# schetamic.net
KiCad netlist of a schematic drawn in EAGLE
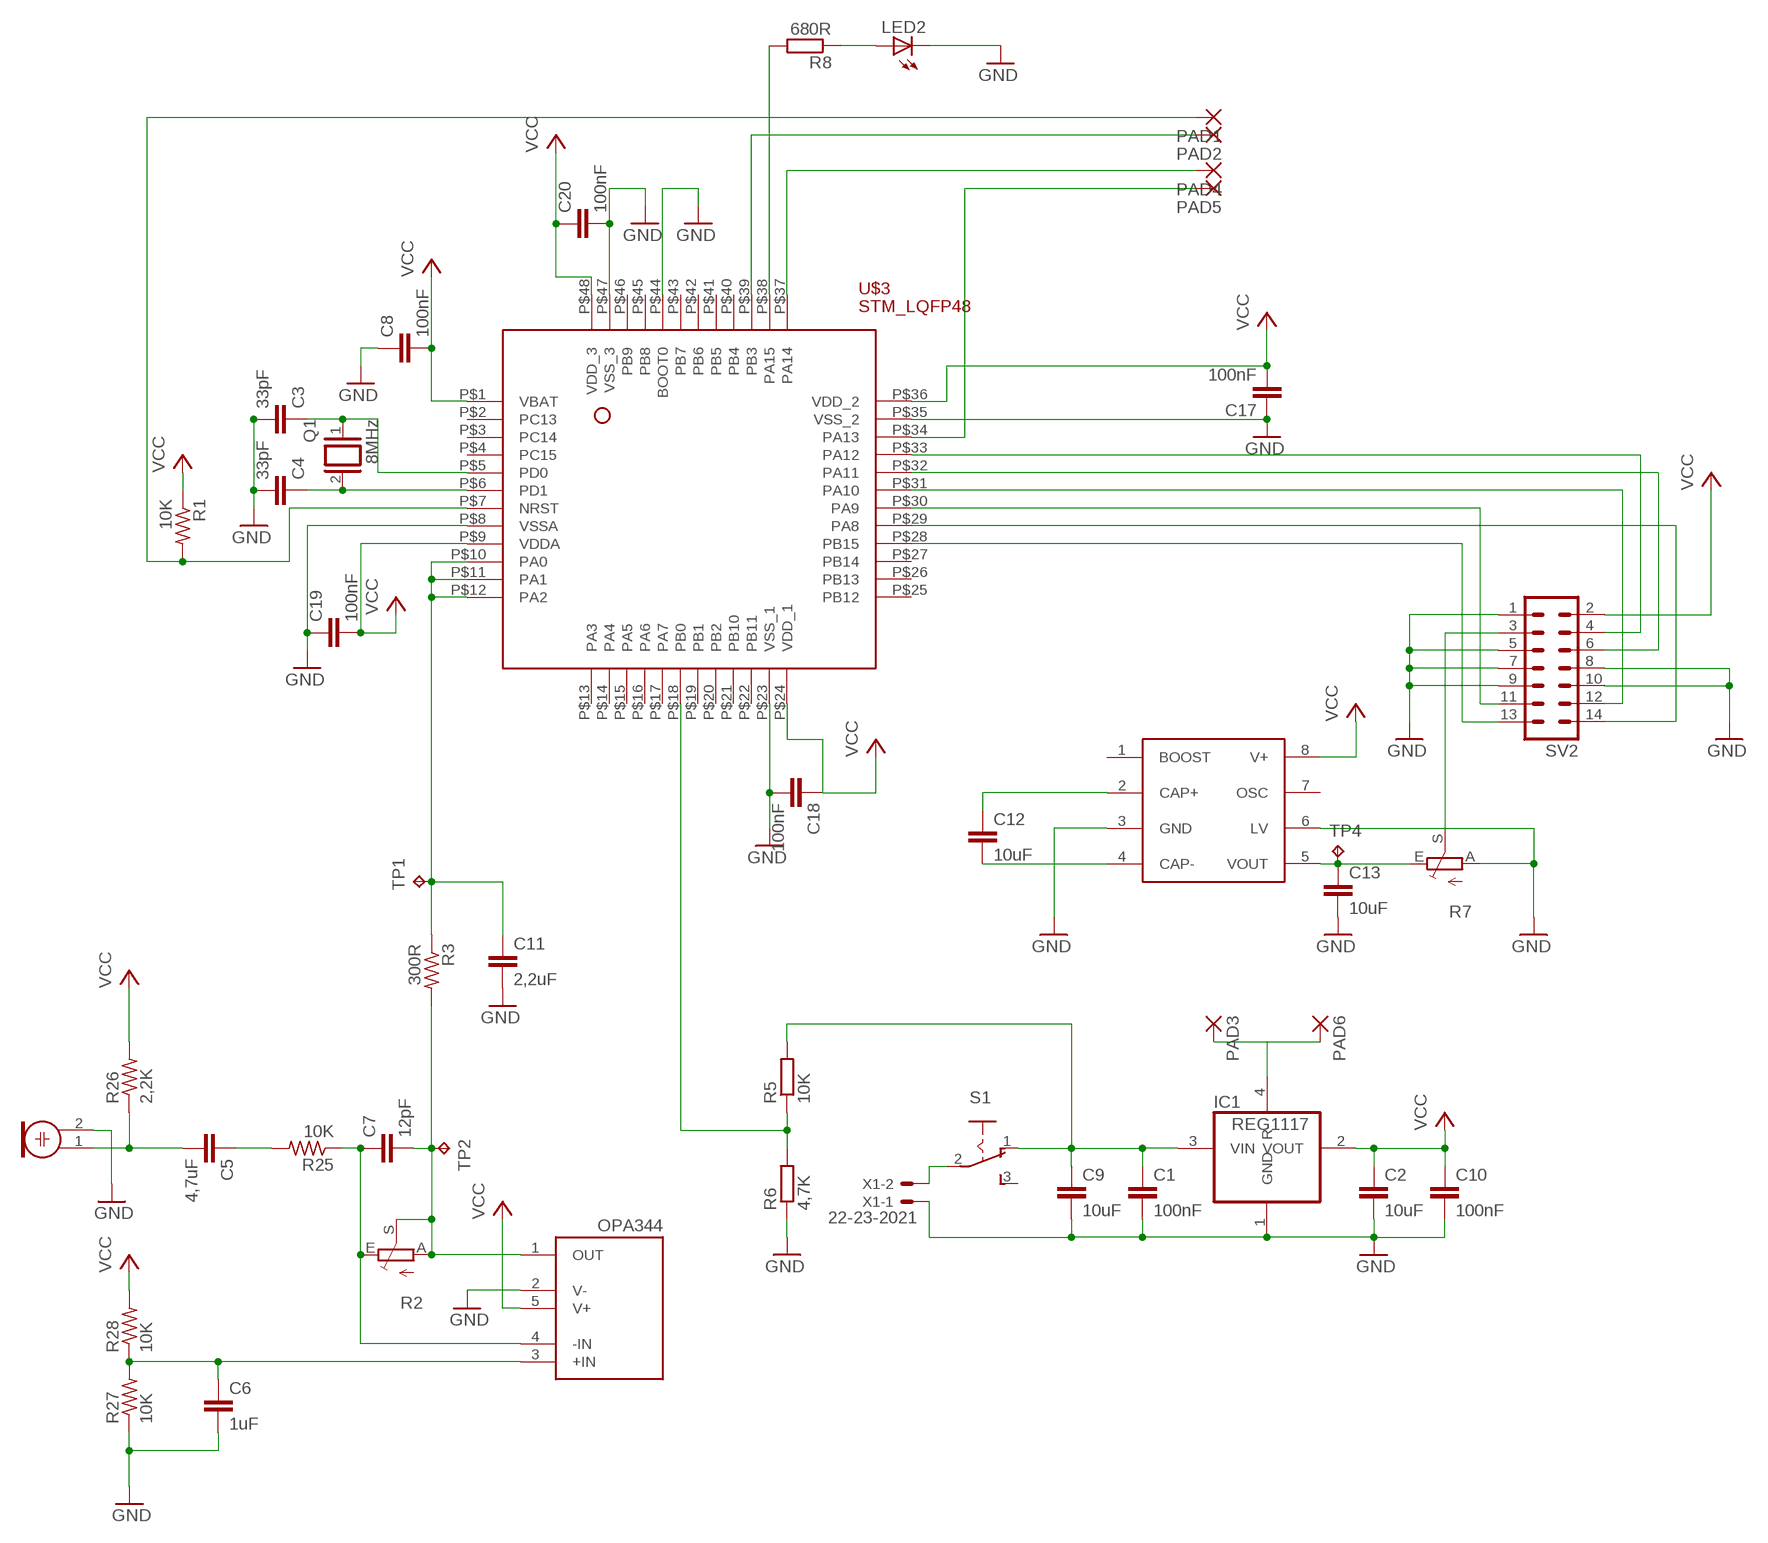
[diagram p0: schematic, sheet 1]

(export (version "E")
  (design (tool "Eeschema 10.0.6"))
  (components
    (comp (ref "C1")
      (value "100nF")
      (footprint "eagle-import:C1206K")
      (libsource (lib "eagle-import") (part "C-EUC1206K"))
    )
    (comp (ref "C2")
      (value "10uF")
      (footprint "eagle-import:C0805")
      (libsource (lib "eagle-import") (part "C-EUC0805"))
    )
    (comp (ref "C3")
      (value "33pF")
      (footprint "eagle-import:C0805")
      (libsource (lib "eagle-import") (part "C-EUC0805"))
    )
    (comp (ref "C4")
      (value "33pF")
      (footprint "eagle-import:C0805")
      (libsource (lib "eagle-import") (part "C-EUC0805"))
    )
    (comp (ref "C5")
      (value "4,7uF")
      (footprint "eagle-import:C0805")
      (libsource (lib "eagle-import") (part "C-EUC0805"))
    )
    (comp (ref "C6")
      (value "1uF")
      (footprint "eagle-import:C1210")
      (libsource (lib "eagle-import") (part "C-EUC1210"))
    )
    (comp (ref "C7")
      (value "12pF")
      (footprint "eagle-import:C0805")
      (libsource (lib "eagle-import") (part "C-EUC0805"))
    )
    (comp (ref "C8")
      (value "100nF")
      (footprint "eagle-import:C1206K")
      (libsource (lib "eagle-import") (part "C-EUC1206K"))
    )
    (comp (ref "C9")
      (value "10uF")
      (footprint "eagle-import:C0805")
      (libsource (lib "eagle-import") (part "C-EUC0805"))
    )
    (comp (ref "C10")
      (value "100nF")
      (footprint "eagle-import:C1206K")
      (libsource (lib "eagle-import") (part "C-EUC1206K"))
    )
    (comp (ref "C11")
      (value "2,2uF")
      (footprint "eagle-import:C1206K")
      (libsource (lib "eagle-import") (part "C-EUC1206K"))
    )
    (comp (ref "C12")
      (value "10uF")
      (footprint "eagle-import:C0805")
      (libsource (lib "eagle-import") (part "C-EUC0805"))
    )
    (comp (ref "C13")
      (value "10uF")
      (footprint "eagle-import:C0805")
      (libsource (lib "eagle-import") (part "C-EUC0805"))
    )
    (comp (ref "C17")
      (value "100nF")
      (footprint "eagle-import:C1206K")
      (libsource (lib "eagle-import") (part "C-EUC1206K"))
    )
    (comp (ref "C18")
      (value "100nF")
      (footprint "eagle-import:C1206K")
      (libsource (lib "eagle-import") (part "C-EUC1206K"))
    )
    (comp (ref "C19")
      (value "100nF")
      (footprint "eagle-import:C1206K")
      (libsource (lib "eagle-import") (part "C-EUC1206K"))
    )
    (comp (ref "C20")
      (value "100nF")
      (footprint "eagle-import:C1206K")
      (libsource (lib "eagle-import") (part "C-EUC1206K"))
    )
    (comp (ref "IC1")
      (value "REG1117")
      (footprint "eagle-import:SOT223")
      (libsource (lib "eagle-import") (part "REG1117"))
    )
    (comp (ref "LED2")
      (value "LED3MM")
      (footprint "eagle-import:LED3MM")
      (libsource (lib "eagle-import") (part "LED3MM"))
    )
    (comp (ref "M1")
      (value "ELECTRET_MICROPHON-F6050AP")
      (footprint "eagle-import:F6050AP")
      (libsource (lib "eagle-import") (part "ELECTRET_MICROPHON-F6050AP"))
    )
    (comp (ref "PAD1")
      (value "SMD2")
      (footprint "eagle-import:SMD1,27-2,54")
      (libsource (lib "eagle-import") (part "SMD2"))
    )
    (comp (ref "PAD2")
      (value "SMD2")
      (footprint "eagle-import:SMD1,27-2,54")
      (libsource (lib "eagle-import") (part "SMD2"))
    )
    (comp (ref "PAD3")
      (value "1,6/0,8")
      (footprint "eagle-import:1,6_0,8")
      (libsource (lib "eagle-import") (part "1,6/0,8"))
    )
    (comp (ref "PAD4")
      (value "SMD2")
      (footprint "eagle-import:SMD1,27-2,54")
      (libsource (lib "eagle-import") (part "SMD2"))
    )
    (comp (ref "PAD5")
      (value "SMD2")
      (footprint "eagle-import:SMD1,27-2,54")
      (libsource (lib "eagle-import") (part "SMD2"))
    )
    (comp (ref "PAD6")
      (value "1,6/0,8")
      (footprint "eagle-import:1,6_0,8")
      (libsource (lib "eagle-import") (part "1,6/0,8"))
    )
    (comp (ref "Q1")
      (value "8MHz")
      (footprint "eagle-import:Q")
      (libsource (lib "eagle-import") (part "XTAL"))
    )
    (comp (ref "R1")
      (value "10K")
      (footprint "eagle-import:R1206@1")
      (libsource (lib "eagle-import") (part "R-US_R1206"))
    )
    (comp (ref "R2")
      (value "TRIM_EU-CA6V")
      (footprint "eagle-import:CA6V")
      (libsource (lib "eagle-import") (part "TRIM_EU-CA6V"))
    )
    (comp (ref "R3")
      (value "300R")
      (footprint "eagle-import:R1206@1")
      (libsource (lib "eagle-import") (part "R-US_R1206"))
    )
    (comp (ref "R5")
      (value "10K")
      (footprint "eagle-import:R1206")
      (libsource (lib "eagle-import") (part "resistor_R-EU_R1206"))
    )
    (comp (ref "R6")
      (value "4,7K")
      (footprint "eagle-import:R1206")
      (libsource (lib "eagle-import") (part "resistor_R-EU_R1206"))
    )
    (comp (ref "R7")
      (value "TRIM_EU-CA6V")
      (footprint "eagle-import:CA6V")
      (libsource (lib "eagle-import") (part "TRIM_EU-CA6V"))
    )
    (comp (ref "R8")
      (value "680R")
      (footprint "eagle-import:M0805")
      (libsource (lib "eagle-import") (part "R-EU_M0805"))
    )
    (comp (ref "R25")
      (value "10K")
      (footprint "eagle-import:R1206@1")
      (libsource (lib "eagle-import") (part "R-US_R1206"))
    )
    (comp (ref "R26")
      (value "2,2K")
      (footprint "eagle-import:R1206@1")
      (libsource (lib "eagle-import") (part "R-US_R1206"))
    )
    (comp (ref "R27")
      (value "10K")
      (footprint "eagle-import:R1206@1")
      (libsource (lib "eagle-import") (part "R-US_R1206"))
    )
    (comp (ref "R28")
      (value "10K")
      (footprint "eagle-import:R1206@1")
      (libsource (lib "eagle-import") (part "R-US_R1206"))
    )
    (comp (ref "S1")
      (value "255SB")
      (footprint "eagle-import:255SB")
      (libsource (lib "eagle-import") (part "255SB"))
    )
    (comp (ref "SV2")
      (value "MA07-2")
      (footprint "eagle-import:MA07-2")
      (libsource (lib "eagle-import") (part "MA07-2"))
    )
    (comp (ref "TP1")
      (value "TPB1,27")
      (footprint "eagle-import:B1,27")
      (libsource (lib "eagle-import") (part "TPB1,27"))
    )
    (comp (ref "TP2")
      (value "TPB1,27")
      (footprint "eagle-import:B1,27")
      (libsource (lib "eagle-import") (part "TPB1,27"))
    )
    (comp (ref "TP4")
      (value "TPB1,27")
      (footprint "eagle-import:B1,27")
      (libsource (lib "eagle-import") (part "TPB1,27"))
    )
    (comp (ref "U$1")
      (value "ICL7660")
      (footprint "eagle-import:SOIC8")
      (libsource (lib "eagle-import") (part "ICL7660"))
    )
    (comp (ref "U$2")
      (value "OPA344")
      (footprint "eagle-import:SOT23-5")
      (libsource (lib "eagle-import") (part "OPA344"))
    )
    (comp (ref "U$3")
      (value "STM_LQFP48")
      (footprint "eagle-import:STM_LQFP48")
      (libsource (lib "eagle-import") (part "STM_LQFP48"))
    )
    (comp (ref "X1")
      (value "22-23-2021")
      (footprint "eagle-import:22-23-2021")
      (fields (field (name "MF") "MOLEX"))
      (libsource (lib "eagle-import") (part "22-23-2021"))
    )
  )
  (nets
    (net (code "1") (name "GND") (class "Default")
      (node (ref "C1") (pin "2") (pinfunction "2_2") (pintype "passive"))
      (node (ref "C10") (pin "2") (pinfunction "2_2") (pintype "passive"))
      (node (ref "C11") (pin "2") (pinfunction "2_2") (pintype "passive"))
      (node (ref "C13") (pin "2") (pinfunction "2_2") (pintype "passive"))
      (node (ref "C17") (pin "1") (pinfunction "1_1") (pintype "passive"))
      (node (ref "C18") (pin "2") (pinfunction "2_2") (pintype "passive"))
      (node (ref "C19") (pin "1") (pinfunction "1_1") (pintype "passive"))
      (node (ref "C2") (pin "2") (pinfunction "2_2") (pintype "passive"))
      (node (ref "C20") (pin "2") (pinfunction "2_2") (pintype "passive"))
      (node (ref "C3") (pin "2") (pinfunction "2_2") (pintype "passive"))
      (node (ref "C4") (pin "2") (pinfunction "2_2") (pintype "passive"))
      (node (ref "C6") (pin "2") (pinfunction "2_2") (pintype "passive"))
      (node (ref "C8") (pin "1") (pinfunction "1_1") (pintype "passive"))
      (node (ref "C9") (pin "2") (pinfunction "2_2") (pintype "passive"))
      (node (ref "IC1") (pin "1") (pinfunction "GND_1") (pintype "power_in"))
      (node (ref "LED2") (pin "K") (pinfunction "C_K") (pintype "passive"))
      (node (ref "M1") (pin "2") (pinfunction "2_2") (pintype "passive"))
      (node (ref "R27") (pin "1") (pinfunction "1_1") (pintype "passive"))
      (node (ref "R6") (pin "1") (pinfunction "1_1") (pintype "passive"))
      (node (ref "R7") (pin "A") (pinfunction "A_A") (pintype "passive"))
      (node (ref "SV2") (pin "1") (pinfunction "1_1") (pintype "passive"))
      (node (ref "SV2") (pin "10") (pinfunction "10_10") (pintype "passive"))
      (node (ref "SV2") (pin "5") (pinfunction "5_5") (pintype "passive"))
      (node (ref "SV2") (pin "7") (pinfunction "7_7") (pintype "passive"))
      (node (ref "SV2") (pin "8") (pinfunction "8_8") (pintype "passive"))
      (node (ref "SV2") (pin "9") (pinfunction "9_9") (pintype "passive"))
      (node (ref "U$1") (pin "3") (pinfunction "GND_3") (pintype "bidirectional"))
      (node (ref "U$1") (pin "6") (pinfunction "LV_6") (pintype "bidirectional"))
      (node (ref "U$2") (pin "2") (pinfunction "V-_2") (pintype "bidirectional"))
      (node (ref "U$3") (pin "P$23") (pinfunction "VSS_1_P$23") (pintype "power_in"))
      (node (ref "U$3") (pin "P$35") (pinfunction "VSS_2_P$35") (pintype "power_in"))
      (node (ref "U$3") (pin "P$44") (pinfunction "BOOT0_P$44") (pintype "input"))
      (node (ref "U$3") (pin "P$47") (pinfunction "VSS_3_P$47") (pintype "power_in"))
      (node (ref "U$3") (pin "P$8") (pinfunction "VSSA_P$8") (pintype "power_in"))
      (node (ref "X1") (pin "1") (pinfunction "S_1") (pintype "passive"))
    )
    (net (code "2") (name "Net-(C5-Pad1)") (class "Default")
      (node (ref "C5") (pin "1") (pinfunction "1_1") (pintype "passive"))
      (node (ref "R25") (pin "2") (pinfunction "2_2") (pintype "passive"))
    )
    (net (code "3") (name "Net-(C5-Pad2)") (class "Default")
      (node (ref "C5") (pin "2") (pinfunction "2_2") (pintype "passive"))
      (node (ref "M1") (pin "1") (pinfunction "1_1") (pintype "passive"))
      (node (ref "R26") (pin "1") (pinfunction "1_1") (pintype "passive"))
    )
    (net (code "4") (name "Net-(IC1-R)") (class "Default")
      (node (ref "IC1") (pin "4") (pinfunction "R_4") (pintype "bidirectional"))
      (node (ref "PAD3") (pin "1") (pinfunction "P_1") (pintype "passive"))
      (node (ref "PAD6") (pin "1") (pinfunction "P_1") (pintype "passive"))
    )
    (net (code "5") (name "Net-(IC1-VIN)") (class "Default")
      (node (ref "C1") (pin "1") (pinfunction "1_1") (pintype "passive"))
      (node (ref "C9") (pin "1") (pinfunction "1_1") (pintype "passive"))
      (node (ref "IC1") (pin "3") (pinfunction "VIN_3") (pintype "input"))
      (node (ref "R5") (pin "2") (pinfunction "2_2") (pintype "passive"))
      (node (ref "S1") (pin "1") (pinfunction "O_1") (pintype "passive"))
    )
    (net (code "6") (name "Net-(LED2-PadA)") (class "Default")
      (node (ref "LED2") (pin "A") (pinfunction "A_A") (pintype "passive"))
      (node (ref "R8") (pin "1") (pinfunction "1_1") (pintype "passive"))
    )
    (net (code "7") (name "Net-(PAD1-P)") (class "Default")
      (node (ref "PAD1") (pin "1") (pinfunction "P_1") (pintype "passive"))
      (node (ref "R1") (pin "2") (pinfunction "2_2") (pintype "passive"))
      (node (ref "U$3") (pin "P$7") (pinfunction "NRST_P$7") (pintype "input"))
    )
    (net (code "8") (name "Net-(PAD2-P)") (class "Default")
      (node (ref "PAD2") (pin "1") (pinfunction "P_1") (pintype "passive"))
      (node (ref "U$3") (pin "P$39") (pinfunction "PB3_P$39") (pintype "bidirectional"))
    )
    (net (code "9") (name "Net-(PAD4-P)") (class "Default")
      (node (ref "PAD4") (pin "1") (pinfunction "P_1") (pintype "passive"))
      (node (ref "U$3") (pin "P$37") (pinfunction "PA14_P$37") (pintype "bidirectional"))
    )
    (net (code "10") (name "Net-(PAD5-P)") (class "Default")
      (node (ref "PAD5") (pin "1") (pinfunction "P_1") (pintype "passive"))
      (node (ref "U$3") (pin "P$34") (pinfunction "PA13_P$34") (pintype "bidirectional"))
    )
    (net (code "11") (name "Net-(R7-PadS)") (class "Default")
      (node (ref "R7") (pin "S") (pinfunction "S_S") (pintype "passive"))
      (node (ref "SV2") (pin "3") (pinfunction "3_3") (pintype "passive"))
    )
    (net (code "12") (name "Net-(S1-P)") (class "Default")
      (node (ref "S1") (pin "2") (pinfunction "P_2") (pintype "passive"))
      (node (ref "X1") (pin "2") (pinfunction "S_2") (pintype "passive"))
    )
    (net (code "13") (name "Net-(U$1-CAP+)") (class "Default")
      (node (ref "C12") (pin "1") (pinfunction "1_1") (pintype "passive"))
      (node (ref "U$1") (pin "2") (pinfunction "CAP+_2") (pintype "bidirectional"))
    )
    (net (code "14") (name "Net-(U$1-CAP-)") (class "Default")
      (node (ref "C12") (pin "2") (pinfunction "2_2") (pintype "passive"))
      (node (ref "U$1") (pin "4") (pinfunction "CAP-_4") (pintype "bidirectional"))
    )
    (net (code "15") (name "Net-(U$1-VOUT)") (class "Default")
      (node (ref "C13") (pin "1") (pinfunction "1_1") (pintype "passive"))
      (node (ref "R7") (pin "E") (pinfunction "E_E") (pintype "passive"))
      (node (ref "TP4") (pin "TP") (pinfunction "TP_TP") (pintype "input"))
      (node (ref "U$1") (pin "5") (pinfunction "VOUT_5") (pintype "bidirectional"))
    )
    (net (code "16") (name "Net-(U$2-+IN)") (class "Default")
      (node (ref "C6") (pin "1") (pinfunction "1_1") (pintype "passive"))
      (node (ref "R27") (pin "2") (pinfunction "2_2") (pintype "passive"))
      (node (ref "R28") (pin "1") (pinfunction "1_1") (pintype "passive"))
      (node (ref "U$2") (pin "3") (pinfunction "+IN_3") (pintype "bidirectional"))
    )
    (net (code "17") (name "Net-(U$2--IN)") (class "Default")
      (node (ref "C7") (pin "1") (pinfunction "1_1") (pintype "passive"))
      (node (ref "R2") (pin "E") (pinfunction "E_E") (pintype "passive"))
      (node (ref "R25") (pin "1") (pinfunction "1_1") (pintype "passive"))
      (node (ref "U$2") (pin "4") (pinfunction "-IN_4") (pintype "bidirectional"))
    )
    (net (code "18") (name "Net-(U$2-OUT)") (class "Default")
      (node (ref "C7") (pin "2") (pinfunction "2_2") (pintype "passive"))
      (node (ref "R2") (pin "A") (pinfunction "A_A") (pintype "passive"))
      (node (ref "R2") (pin "S") (pinfunction "S_S") (pintype "passive"))
      (node (ref "R3") (pin "2") (pinfunction "2_2") (pintype "passive"))
      (node (ref "TP2") (pin "TP") (pinfunction "TP_TP") (pintype "input"))
      (node (ref "U$2") (pin "1") (pinfunction "OUT_1") (pintype "bidirectional"))
    )
    (net (code "19") (name "Net-(U$3-PA0)") (class "Default")
      (node (ref "C11") (pin "1") (pinfunction "1_1") (pintype "passive"))
      (node (ref "R3") (pin "1") (pinfunction "1_1") (pintype "passive"))
      (node (ref "TP1") (pin "TP") (pinfunction "TP_TP") (pintype "input"))
      (node (ref "U$3") (pin "P$10") (pinfunction "PA0_P$10") (pintype "bidirectional"))
      (node (ref "U$3") (pin "P$11") (pinfunction "PA1_P$11") (pintype "bidirectional"))
      (node (ref "U$3") (pin "P$12") (pinfunction "PA2_P$12") (pintype "bidirectional"))
    )
    (net (code "20") (name "Net-(U$3-PA8)") (class "Default")
      (node (ref "SV2") (pin "14") (pinfunction "14_14") (pintype "passive"))
      (node (ref "U$3") (pin "P$29") (pinfunction "PA8_P$29") (pintype "bidirectional"))
    )
    (net (code "21") (name "Net-(U$3-PA9)") (class "Default")
      (node (ref "SV2") (pin "11") (pinfunction "11_11") (pintype "passive"))
      (node (ref "U$3") (pin "P$30") (pinfunction "PA9_P$30") (pintype "bidirectional"))
    )
    (net (code "22") (name "Net-(U$3-PA10)") (class "Default")
      (node (ref "SV2") (pin "12") (pinfunction "12_12") (pintype "passive"))
      (node (ref "U$3") (pin "P$31") (pinfunction "PA10_P$31") (pintype "bidirectional"))
    )
    (net (code "23") (name "Net-(U$3-PA11)") (class "Default")
      (node (ref "SV2") (pin "6") (pinfunction "6_6") (pintype "passive"))
      (node (ref "U$3") (pin "P$32") (pinfunction "PA11_P$32") (pintype "bidirectional"))
    )
    (net (code "24") (name "Net-(U$3-PA12)") (class "Default")
      (node (ref "SV2") (pin "4") (pinfunction "4_4") (pintype "passive"))
      (node (ref "U$3") (pin "P$33") (pinfunction "PA12_P$33") (pintype "bidirectional"))
    )
    (net (code "25") (name "Net-(U$3-PA15)") (class "Default")
      (node (ref "R8") (pin "2") (pinfunction "2_2") (pintype "passive"))
      (node (ref "U$3") (pin "P$38") (pinfunction "PA15_P$38") (pintype "bidirectional"))
    )
    (net (code "26") (name "Net-(U$3-PB0)") (class "Default")
      (node (ref "R5") (pin "1") (pinfunction "1_1") (pintype "passive"))
      (node (ref "R6") (pin "2") (pinfunction "2_2") (pintype "passive"))
      (node (ref "U$3") (pin "P$18") (pinfunction "PB0_P$18") (pintype "bidirectional"))
    )
    (net (code "27") (name "Net-(U$3-PB15)") (class "Default")
      (node (ref "SV2") (pin "13") (pinfunction "13_13") (pintype "passive"))
      (node (ref "U$3") (pin "P$28") (pinfunction "PB15_P$28") (pintype "bidirectional"))
    )
    (net (code "28") (name "Net-(U$3-PD0)") (class "Default")
      (node (ref "C3") (pin "1") (pinfunction "1_1") (pintype "passive"))
      (node (ref "Q1") (pin "1") (pinfunction "1_1") (pintype "passive"))
      (node (ref "U$3") (pin "P$5") (pinfunction "PD0_P$5") (pintype "input"))
    )
    (net (code "29") (name "Net-(U$3-PD1)") (class "Default")
      (node (ref "C4") (pin "1") (pinfunction "1_1") (pintype "passive"))
      (node (ref "Q1") (pin "2") (pinfunction "2_2") (pintype "passive"))
      (node (ref "U$3") (pin "P$6") (pinfunction "PD1_P$6") (pintype "output"))
    )
    (net (code "30") (name "VCC") (class "Default")
      (node (ref "C10") (pin "1") (pinfunction "1_1") (pintype "passive"))
      (node (ref "C17") (pin "2") (pinfunction "2_2") (pintype "passive"))
      (node (ref "C18") (pin "1") (pinfunction "1_1") (pintype "passive"))
      (node (ref "C19") (pin "2") (pinfunction "2_2") (pintype "passive"))
      (node (ref "C2") (pin "1") (pinfunction "1_1") (pintype "passive"))
      (node (ref "C20") (pin "1") (pinfunction "1_1") (pintype "passive"))
      (node (ref "C8") (pin "2") (pinfunction "2_2") (pintype "passive"))
      (node (ref "IC1") (pin "2") (pinfunction "VOUT_2") (pintype "output"))
      (node (ref "R1") (pin "1") (pinfunction "1_1") (pintype "passive"))
      (node (ref "R26") (pin "2") (pinfunction "2_2") (pintype "passive"))
      (node (ref "R28") (pin "2") (pinfunction "2_2") (pintype "passive"))
      (node (ref "SV2") (pin "2") (pinfunction "2_2") (pintype "passive"))
      (node (ref "U$1") (pin "8") (pinfunction "V+_8") (pintype "bidirectional"))
      (node (ref "U$2") (pin "5") (pinfunction "V+_5") (pintype "bidirectional"))
      (node (ref "U$3") (pin "P$1") (pinfunction "VBAT_P$1") (pintype "power_in"))
      (node (ref "U$3") (pin "P$24") (pinfunction "VDD_1_P$24") (pintype "power_in"))
      (node (ref "U$3") (pin "P$36") (pinfunction "VDD_2_P$36") (pintype "power_in"))
      (node (ref "U$3") (pin "P$48") (pinfunction "VDD_3_P$48") (pintype "power_in"))
      (node (ref "U$3") (pin "P$9") (pinfunction "VDDA_P$9") (pintype "power_in"))
    )
    (net (code "31") (name "unconnected-(S1-S-Pad3)") (class "Default")
      (node (ref "S1") (pin "3") (pinfunction "S_3") (pintype "passive"))
    )
    (net (code "32") (name "unconnected-(U$1-BOOST-Pad1)") (class "Default")
      (node (ref "U$1") (pin "1") (pinfunction "BOOST_1") (pintype "bidirectional"))
    )
    (net (code "33") (name "unconnected-(U$1-OSC-Pad7)") (class "Default")
      (node (ref "U$1") (pin "7") (pinfunction "OSC_7") (pintype "bidirectional"))
    )
    (net (code "34") (name "unconnected-(U$3-PA3-PadP$13)") (class "Default")
      (node (ref "U$3") (pin "P$13") (pinfunction "PA3_P$13") (pintype "bidirectional"))
    )
    (net (code "35") (name "unconnected-(U$3-PA4-PadP$14)") (class "Default")
      (node (ref "U$3") (pin "P$14") (pinfunction "PA4_P$14") (pintype "bidirectional"))
    )
    (net (code "36") (name "unconnected-(U$3-PA5-PadP$15)") (class "Default")
      (node (ref "U$3") (pin "P$15") (pinfunction "PA5_P$15") (pintype "bidirectional"))
    )
    (net (code "37") (name "unconnected-(U$3-PA6-PadP$16)") (class "Default")
      (node (ref "U$3") (pin "P$16") (pinfunction "PA6_P$16") (pintype "bidirectional"))
    )
    (net (code "38") (name "unconnected-(U$3-PA7-PadP$17)") (class "Default")
      (node (ref "U$3") (pin "P$17") (pinfunction "PA7_P$17") (pintype "bidirectional"))
    )
    (net (code "39") (name "unconnected-(U$3-PB1-PadP$19)") (class "Default")
      (node (ref "U$3") (pin "P$19") (pinfunction "PB1_P$19") (pintype "bidirectional"))
    )
    (net (code "40") (name "unconnected-(U$3-PB2-PadP$20)") (class "Default")
      (node (ref "U$3") (pin "P$20") (pinfunction "PB2_P$20") (pintype "bidirectional"))
    )
    (net (code "41") (name "unconnected-(U$3-PB4-PadP$40)") (class "Default")
      (node (ref "U$3") (pin "P$40") (pinfunction "PB4_P$40") (pintype "bidirectional"))
    )
    (net (code "42") (name "unconnected-(U$3-PB5-PadP$41)") (class "Default")
      (node (ref "U$3") (pin "P$41") (pinfunction "PB5_P$41") (pintype "bidirectional"))
    )
    (net (code "43") (name "unconnected-(U$3-PB6-PadP$42)") (class "Default")
      (node (ref "U$3") (pin "P$42") (pinfunction "PB6_P$42") (pintype "bidirectional"))
    )
    (net (code "44") (name "unconnected-(U$3-PB7-PadP$43)") (class "Default")
      (node (ref "U$3") (pin "P$43") (pinfunction "PB7_P$43") (pintype "bidirectional"))
    )
    (net (code "45") (name "unconnected-(U$3-PB8-PadP$45)") (class "Default")
      (node (ref "U$3") (pin "P$45") (pinfunction "PB8_P$45") (pintype "bidirectional"))
    )
    (net (code "46") (name "unconnected-(U$3-PB9-PadP$46)") (class "Default")
      (node (ref "U$3") (pin "P$46") (pinfunction "PB9_P$46") (pintype "bidirectional"))
    )
    (net (code "47") (name "unconnected-(U$3-PB10-PadP$21)") (class "Default")
      (node (ref "U$3") (pin "P$21") (pinfunction "PB10_P$21") (pintype "bidirectional"))
    )
    (net (code "48") (name "unconnected-(U$3-PB11-PadP$22)") (class "Default")
      (node (ref "U$3") (pin "P$22") (pinfunction "PB11_P$22") (pintype "bidirectional"))
    )
    (net (code "49") (name "unconnected-(U$3-PB12-PadP$25)") (class "Default")
      (node (ref "U$3") (pin "P$25") (pinfunction "PB12_P$25") (pintype "bidirectional"))
    )
    (net (code "50") (name "unconnected-(U$3-PB13-PadP$26)") (class "Default")
      (node (ref "U$3") (pin "P$26") (pinfunction "PB13_P$26") (pintype "bidirectional"))
    )
    (net (code "51") (name "unconnected-(U$3-PB14-PadP$27)") (class "Default")
      (node (ref "U$3") (pin "P$27") (pinfunction "PB14_P$27") (pintype "bidirectional"))
    )
    (net (code "52") (name "unconnected-(U$3-PC13-PadP$2)") (class "Default")
      (node (ref "U$3") (pin "P$2") (pinfunction "PC13_P$2") (pintype "bidirectional"))
    )
    (net (code "53") (name "unconnected-(U$3-PC14-PadP$3)") (class "Default")
      (node (ref "U$3") (pin "P$3") (pinfunction "PC14_P$3") (pintype "input"))
    )
    (net (code "54") (name "unconnected-(U$3-PC15-PadP$4)") (class "Default")
      (node (ref "U$3") (pin "P$4") (pinfunction "PC15_P$4") (pintype "output"))
    )
  )
)
